# Main_sheet.net
KiCad netlist of a schematic drawn in Altium Designer
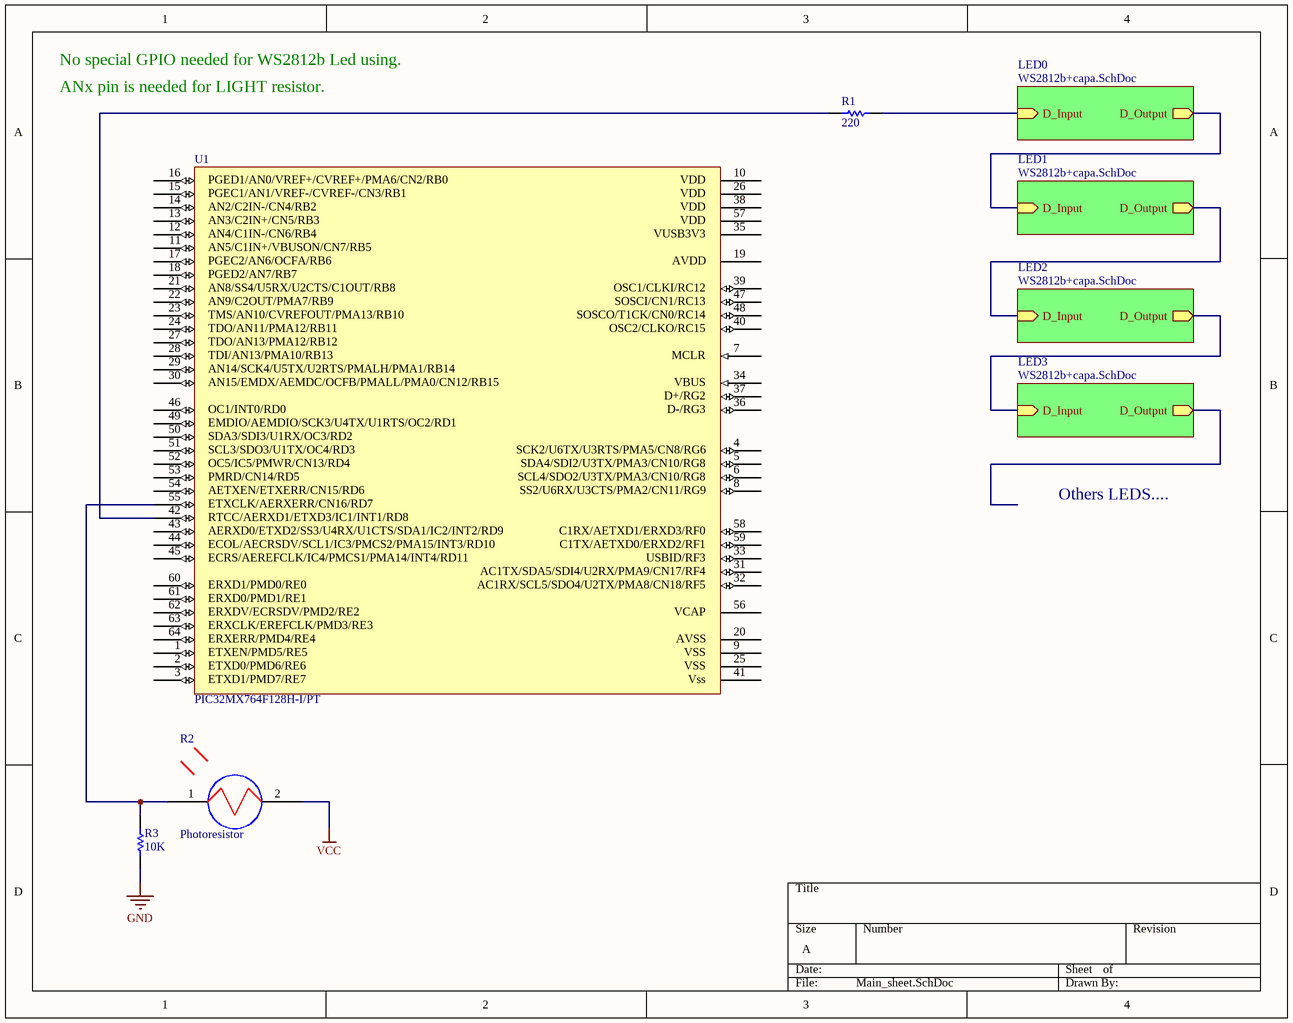
[diagram p0: Main_sheet.SchDoc]

(export (version "E")
  (design (tool "Eeschema 10.0.6"))
  (components
    (comp (ref "R1")
      (value "220")
      (footprint "AXIAL-0.3")
      (description "Resistor")
      (fields (field (name "PUBLISHER") "Altium Limited"))
      (libsource (lib "Miscellaneous Devices") (part "Res1"))
    )
    (comp (ref "R2") (value "Photoresistor") (libsource (lib "Schlib1") (part "Photoresistor")))
    (comp (ref "R3")
      (value "10K")
      (footprint "AXIAL-0.3")
      (description "Resistor")
      (fields (field (name "PUBLISHER") "Altium Limited"))
      (libsource (lib "Miscellaneous Devices") (part "Res1"))
    )
    (comp (ref "U1")
      (value "PIC32MX764F128H-I/PT")
      (description "PIC32MX764F128H")
      (libsource (lib "PIC") (part "PIC32MX764F128H-I/PT"))
    )
  )
  (nets
    (net (code "1") (name "/D_Input") (class "Default")
      (node (ref "R1") (pin "2") (pinfunction "2_2") (pintype "passive"))
    )
    (net (code "6") (name "GND") (class "Default")
      (node (ref "R3") (pin "1") (pinfunction "1_1") (pintype "passive"))
    )
    (net (code "7") (name "Net-(R1-Pad1)") (class "Default")
      (node (ref "R1") (pin "1") (pinfunction "1_1") (pintype "passive"))
      (node (ref "U1") (pin "42") (pinfunction "42_42") (pintype "bidirectional"))
    )
    (net (code "8") (name "Net-(R2-Pad1)") (class "Default")
      (node (ref "R2") (pin "1") (pintype "passive"))
      (node (ref "R3") (pin "2") (pinfunction "2_2") (pintype "passive"))
      (node (ref "U1") (pin "55") (pinfunction "55_55") (pintype "bidirectional"))
    )
    (net (code "9") (name "VCC") (class "Default") (node (ref "R2") (pin "2") (pintype "passive")))
    (net (code "10") (name "unconnected-(U1-Pad1)") (class "Default")
      (node (ref "U1") (pin "1") (pinfunction "1_1") (pintype "bidirectional"))
    )
    (net (code "11") (name "unconnected-(U1-Pad2)") (class "Default")
      (node (ref "U1") (pin "2") (pinfunction "2_2") (pintype "bidirectional"))
    )
    (net (code "12") (name "unconnected-(U1-Pad3)") (class "Default")
      (node (ref "U1") (pin "3") (pinfunction "3_3") (pintype "bidirectional"))
    )
    (net (code "13") (name "unconnected-(U1-Pad4)") (class "Default")
      (node (ref "U1") (pin "4") (pinfunction "4_4") (pintype "bidirectional"))
    )
    (net (code "14") (name "unconnected-(U1-Pad5)") (class "Default")
      (node (ref "U1") (pin "5") (pinfunction "5_5") (pintype "bidirectional"))
    )
    (net (code "15") (name "unconnected-(U1-Pad6)") (class "Default")
      (node (ref "U1") (pin "6") (pinfunction "6_6") (pintype "bidirectional"))
    )
    (net (code "16") (name "unconnected-(U1-Pad7)") (class "Default")
      (node (ref "U1") (pin "7") (pinfunction "7_7") (pintype "input"))
    )
    (net (code "17") (name "unconnected-(U1-Pad8)") (class "Default")
      (node (ref "U1") (pin "8") (pinfunction "8_8") (pintype "bidirectional"))
    )
    (net (code "18") (name "unconnected-(U1-Pad9)") (class "Default")
      (node (ref "U1") (pin "9") (pinfunction "9_9") (pintype "power_in"))
    )
    (net (code "19") (name "unconnected-(U1-Pad10)") (class "Default")
      (node (ref "U1") (pin "10") (pinfunction "10_10") (pintype "power_in"))
    )
    (net (code "20") (name "unconnected-(U1-Pad11)") (class "Default")
      (node (ref "U1") (pin "11") (pinfunction "11_11") (pintype "bidirectional"))
    )
    (net (code "21") (name "unconnected-(U1-Pad12)") (class "Default")
      (node (ref "U1") (pin "12") (pinfunction "12_12") (pintype "bidirectional"))
    )
    (net (code "22") (name "unconnected-(U1-Pad13)") (class "Default")
      (node (ref "U1") (pin "13") (pinfunction "13_13") (pintype "bidirectional"))
    )
    (net (code "23") (name "unconnected-(U1-Pad14)") (class "Default")
      (node (ref "U1") (pin "14") (pinfunction "14_14") (pintype "bidirectional"))
    )
    (net (code "24") (name "unconnected-(U1-Pad15)") (class "Default")
      (node (ref "U1") (pin "15") (pinfunction "15_15") (pintype "bidirectional"))
    )
    (net (code "25") (name "unconnected-(U1-Pad16)") (class "Default")
      (node (ref "U1") (pin "16") (pinfunction "16_16") (pintype "bidirectional"))
    )
    (net (code "26") (name "unconnected-(U1-Pad17)") (class "Default")
      (node (ref "U1") (pin "17") (pinfunction "17_17") (pintype "bidirectional"))
    )
    (net (code "27") (name "unconnected-(U1-Pad18)") (class "Default")
      (node (ref "U1") (pin "18") (pinfunction "18_18") (pintype "bidirectional"))
    )
    (net (code "28") (name "unconnected-(U1-Pad19)") (class "Default")
      (node (ref "U1") (pin "19") (pinfunction "19_19") (pintype "power_in"))
    )
    (net (code "29") (name "unconnected-(U1-Pad20)") (class "Default")
      (node (ref "U1") (pin "20") (pinfunction "20_20") (pintype "power_in"))
    )
    (net (code "30") (name "unconnected-(U1-Pad21)") (class "Default")
      (node (ref "U1") (pin "21") (pinfunction "21_21") (pintype "bidirectional"))
    )
    (net (code "31") (name "unconnected-(U1-Pad22)") (class "Default")
      (node (ref "U1") (pin "22") (pinfunction "22_22") (pintype "bidirectional"))
    )
    (net (code "32") (name "unconnected-(U1-Pad23)") (class "Default")
      (node (ref "U1") (pin "23") (pinfunction "23_23") (pintype "bidirectional"))
    )
    (net (code "33") (name "unconnected-(U1-Pad24)") (class "Default")
      (node (ref "U1") (pin "24") (pinfunction "24_24") (pintype "bidirectional"))
    )
    (net (code "34") (name "unconnected-(U1-Pad25)") (class "Default")
      (node (ref "U1") (pin "25") (pinfunction "25_25") (pintype "power_in"))
    )
    (net (code "35") (name "unconnected-(U1-Pad26)") (class "Default")
      (node (ref "U1") (pin "26") (pinfunction "26_26") (pintype "power_in"))
    )
    (net (code "36") (name "unconnected-(U1-Pad27)") (class "Default")
      (node (ref "U1") (pin "27") (pinfunction "27_27") (pintype "bidirectional"))
    )
    (net (code "37") (name "unconnected-(U1-Pad28)") (class "Default")
      (node (ref "U1") (pin "28") (pinfunction "28_28") (pintype "bidirectional"))
    )
    (net (code "38") (name "unconnected-(U1-Pad29)") (class "Default")
      (node (ref "U1") (pin "29") (pinfunction "29_29") (pintype "bidirectional"))
    )
    (net (code "39") (name "unconnected-(U1-Pad30)") (class "Default")
      (node (ref "U1") (pin "30") (pinfunction "30_30") (pintype "bidirectional"))
    )
    (net (code "40") (name "unconnected-(U1-Pad31)") (class "Default")
      (node (ref "U1") (pin "31") (pinfunction "31_31") (pintype "bidirectional"))
    )
    (net (code "41") (name "unconnected-(U1-Pad32)") (class "Default")
      (node (ref "U1") (pin "32") (pinfunction "32_32") (pintype "bidirectional"))
    )
    (net (code "42") (name "unconnected-(U1-Pad33)") (class "Default")
      (node (ref "U1") (pin "33") (pinfunction "33_33") (pintype "bidirectional"))
    )
    (net (code "43") (name "unconnected-(U1-Pad34)") (class "Default")
      (node (ref "U1") (pin "34") (pinfunction "34_34") (pintype "input"))
    )
    (net (code "44") (name "unconnected-(U1-Pad35)") (class "Default")
      (node (ref "U1") (pin "35") (pinfunction "35_35") (pintype "power_in"))
    )
    (net (code "45") (name "unconnected-(U1-Pad36)") (class "Default")
      (node (ref "U1") (pin "36") (pinfunction "36_36") (pintype "bidirectional"))
    )
    (net (code "46") (name "unconnected-(U1-Pad37)") (class "Default")
      (node (ref "U1") (pin "37") (pinfunction "37_37") (pintype "bidirectional"))
    )
    (net (code "47") (name "unconnected-(U1-Pad38)") (class "Default")
      (node (ref "U1") (pin "38") (pinfunction "38_38") (pintype "power_in"))
    )
    (net (code "48") (name "unconnected-(U1-Pad39)") (class "Default")
      (node (ref "U1") (pin "39") (pinfunction "39_39") (pintype "bidirectional"))
    )
    (net (code "49") (name "unconnected-(U1-Pad40)") (class "Default")
      (node (ref "U1") (pin "40") (pinfunction "40_40") (pintype "bidirectional"))
    )
    (net (code "50") (name "unconnected-(U1-Pad41)") (class "Default")
      (node (ref "U1") (pin "41") (pinfunction "41_41") (pintype "power_in"))
    )
    (net (code "51") (name "unconnected-(U1-Pad43)") (class "Default")
      (node (ref "U1") (pin "43") (pinfunction "43_43") (pintype "bidirectional"))
    )
    (net (code "52") (name "unconnected-(U1-Pad44)") (class "Default")
      (node (ref "U1") (pin "44") (pinfunction "44_44") (pintype "bidirectional"))
    )
    (net (code "53") (name "unconnected-(U1-Pad45)") (class "Default")
      (node (ref "U1") (pin "45") (pinfunction "45_45") (pintype "bidirectional"))
    )
    (net (code "54") (name "unconnected-(U1-Pad46)") (class "Default")
      (node (ref "U1") (pin "46") (pinfunction "46_46") (pintype "bidirectional"))
    )
    (net (code "55") (name "unconnected-(U1-Pad47)") (class "Default")
      (node (ref "U1") (pin "47") (pinfunction "47_47") (pintype "bidirectional"))
    )
    (net (code "56") (name "unconnected-(U1-Pad48)") (class "Default")
      (node (ref "U1") (pin "48") (pinfunction "48_48") (pintype "bidirectional"))
    )
    (net (code "57") (name "unconnected-(U1-Pad49)") (class "Default")
      (node (ref "U1") (pin "49") (pinfunction "49_49") (pintype "bidirectional"))
    )
    (net (code "58") (name "unconnected-(U1-Pad50)") (class "Default")
      (node (ref "U1") (pin "50") (pinfunction "50_50") (pintype "bidirectional"))
    )
    (net (code "59") (name "unconnected-(U1-Pad51)") (class "Default")
      (node (ref "U1") (pin "51") (pinfunction "51_51") (pintype "bidirectional"))
    )
    (net (code "60") (name "unconnected-(U1-Pad52)") (class "Default")
      (node (ref "U1") (pin "52") (pinfunction "52_52") (pintype "bidirectional"))
    )
    (net (code "61") (name "unconnected-(U1-Pad53)") (class "Default")
      (node (ref "U1") (pin "53") (pinfunction "53_53") (pintype "bidirectional"))
    )
    (net (code "62") (name "unconnected-(U1-Pad54)") (class "Default")
      (node (ref "U1") (pin "54") (pinfunction "54_54") (pintype "bidirectional"))
    )
    (net (code "63") (name "unconnected-(U1-Pad56)") (class "Default")
      (node (ref "U1") (pin "56") (pinfunction "56_56") (pintype "power_in"))
    )
    (net (code "64") (name "unconnected-(U1-Pad57)") (class "Default")
      (node (ref "U1") (pin "57") (pinfunction "57_57") (pintype "power_in"))
    )
    (net (code "65") (name "unconnected-(U1-Pad58)") (class "Default")
      (node (ref "U1") (pin "58") (pinfunction "58_58") (pintype "bidirectional"))
    )
    (net (code "66") (name "unconnected-(U1-Pad59)") (class "Default")
      (node (ref "U1") (pin "59") (pinfunction "59_59") (pintype "bidirectional"))
    )
    (net (code "67") (name "unconnected-(U1-Pad60)") (class "Default")
      (node (ref "U1") (pin "60") (pinfunction "60_60") (pintype "bidirectional"))
    )
    (net (code "68") (name "unconnected-(U1-Pad61)") (class "Default")
      (node (ref "U1") (pin "61") (pinfunction "61_61") (pintype "bidirectional"))
    )
    (net (code "69") (name "unconnected-(U1-Pad62)") (class "Default")
      (node (ref "U1") (pin "62") (pinfunction "62_62") (pintype "bidirectional"))
    )
    (net (code "70") (name "unconnected-(U1-Pad63)") (class "Default")
      (node (ref "U1") (pin "63") (pinfunction "63_63") (pintype "bidirectional"))
    )
    (net (code "71") (name "unconnected-(U1-Pad64)") (class "Default")
      (node (ref "U1") (pin "64") (pinfunction "64_64") (pintype "bidirectional"))
    )
  )
)
